# RCM-Comm_v1_no_ethernet.net
KiCad netlist of a schematic drawn in EAGLE
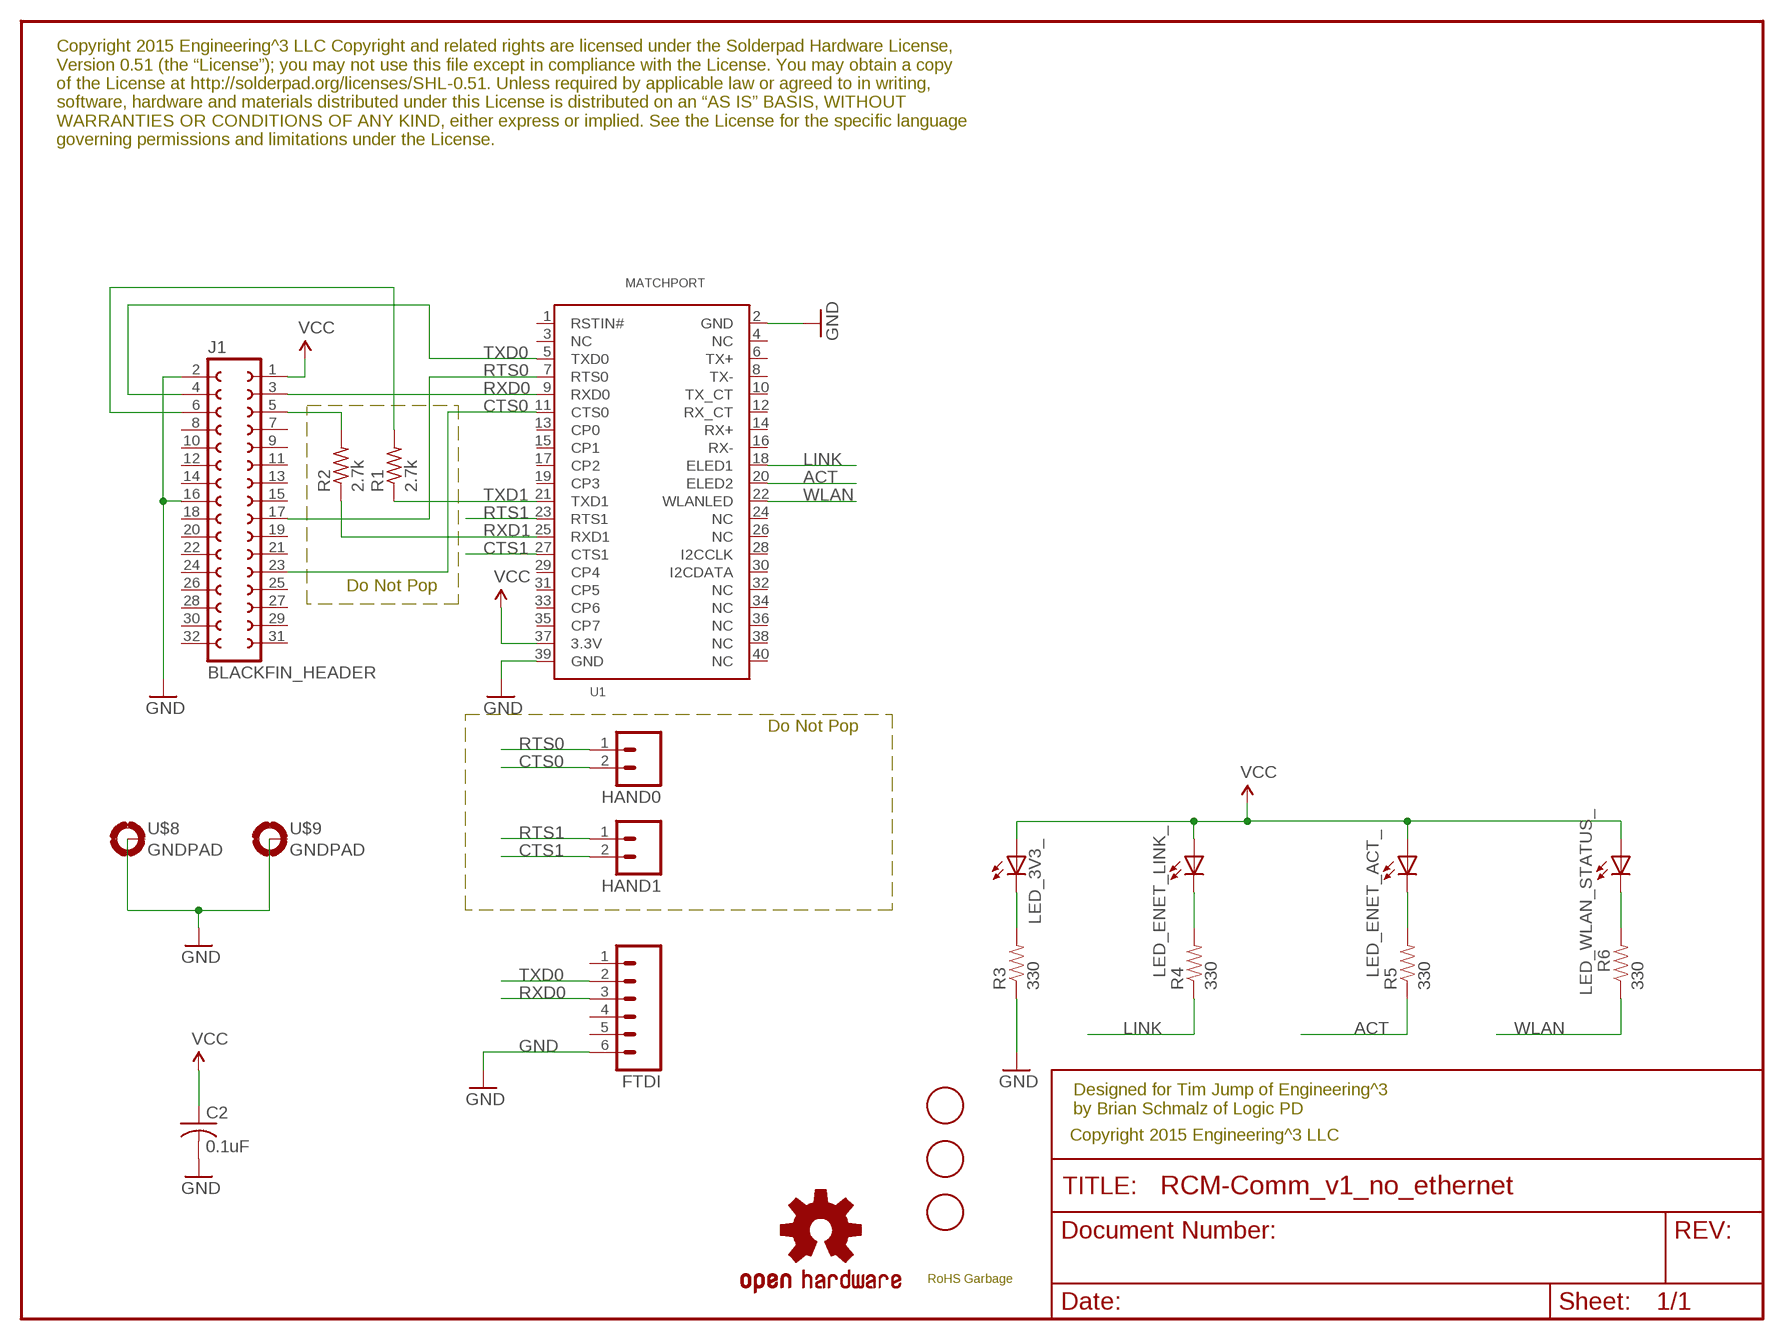
[diagram p0: schematic, sheet 1]

(export (version "E")
  (design (tool "Eeschema 10.0.6"))
  (components
    (comp (ref "C2")
      (value "0.1uF")
      (footprint "eagle-import:C0603")
      (libsource (lib "eagle-import") (part "C-USC0603"))
    )
    (comp (ref "FID1")
      (value "FIDUCIAL")
      (footprint "eagle-import:FIDUCIAL_1MM")
      (libsource (lib "eagle-import") (part "FIDUCIAL"))
    )
    (comp (ref "FID2")
      (value "FIDUCIAL")
      (footprint "eagle-import:FIDUCIAL_1MM")
      (libsource (lib "eagle-import") (part "FIDUCIAL"))
    )
    (comp (ref "FID3")
      (value "FIDUCIAL")
      (footprint "eagle-import:FIDUCIAL_1MM")
      (libsource (lib "eagle-import") (part "FIDUCIAL"))
    )
    (comp (ref "FTDI")
      (value "M06SIP")
      (footprint "eagle-import:1X06")
      (libsource (lib "eagle-import") (part "M06SIP"))
    )
    (comp (ref "HAND0")
      (value "M02PTH")
      (footprint "eagle-import:1X02")
      (libsource (lib "eagle-import") (part "M02PTH"))
    )
    (comp (ref "HAND1")
      (value "M02PTH")
      (footprint "eagle-import:1X02")
      (libsource (lib "eagle-import") (part "M02PTH"))
    )
    (comp (ref "J1")
      (value "BLACKFIN_HEADER")
      (footprint "eagle-import:2X16")
      (libsource (lib "eagle-import") (part "BLACKFIN_HEADER"))
    )
    (comp (ref "LED_3V3_")
      (value "LED0603")
      (footprint "eagle-import:LED-0603")
      (libsource (lib "eagle-import") (part "LED0603"))
    )
    (comp (ref "LED_ENET_ACT_")
      (value "LED0603")
      (footprint "eagle-import:LED-0603")
      (libsource (lib "eagle-import") (part "LED0603"))
    )
    (comp (ref "LED_ENET_LINK_")
      (value "LED0603")
      (footprint "eagle-import:LED-0603")
      (libsource (lib "eagle-import") (part "LED0603"))
    )
    (comp (ref "LED_WLAN_STATUS_")
      (value "LED0603")
      (footprint "eagle-import:LED-0603")
      (libsource (lib "eagle-import") (part "LED0603"))
    )
    (comp (ref "LOGO1")
      (value "OSHW-LOGOM")
      (footprint "eagle-import:OSHW-LOGO-M")
      (libsource (lib "eagle-import") (part "OSHW-LOGOM"))
    )
    (comp (ref "R1")
      (value "2.7k")
      (footprint "eagle-import:0207_10")
      (libsource (lib "eagle-import") (part "R-US_0207/10"))
    )
    (comp (ref "R2")
      (value "2.7k")
      (footprint "eagle-import:0207_10")
      (libsource (lib "eagle-import") (part "R-US_0207/10"))
    )
    (comp (ref "R3")
      (value "330")
      (footprint "eagle-import:0603-RES")
      (libsource (lib "eagle-import") (part "RESISTOR0603-RES"))
    )
    (comp (ref "R4")
      (value "330")
      (footprint "eagle-import:0603-RES")
      (libsource (lib "eagle-import") (part "RESISTOR0603-RES"))
    )
    (comp (ref "R5")
      (value "330")
      (footprint "eagle-import:0603-RES")
      (libsource (lib "eagle-import") (part "RESISTOR0603-RES"))
    )
    (comp (ref "R6")
      (value "330")
      (footprint "eagle-import:0603-RES")
      (libsource (lib "eagle-import") (part "RESISTOR0603-RES"))
    )
    (comp (ref "U$3")
      (value "ROHS_GARBAGE")
      (footprint "eagle-import:ROHS_GARBAGE_5MM")
      (libsource (lib "eagle-import") (part "ROHS_GARBAGE"))
    )
    (comp (ref "U$8")
      (value "GNDPAD")
      (footprint "eagle-import:GNDPAD")
      (libsource (lib "eagle-import") (part "GNDPAD"))
    )
    (comp (ref "U$9")
      (value "GNDPAD")
      (footprint "eagle-import:GNDPAD")
      (libsource (lib "eagle-import") (part "GNDPAD"))
    )
    (comp (ref "U1")
      (value "MATCHPORT")
      (footprint "eagle-import:MATCHPORT_LAYOUT")
      (libsource (lib "eagle-import") (part "MATCHPORT"))
    )
  )
  (nets
    (net (code "1") (name "/ACT") (class "Default")
      (node (ref "R5") (pin "1") (pinfunction "1_1") (pintype "passive"))
      (node (ref "U1") (pin "20") (pinfunction "ELED2_20") (pintype "bidirectional"))
    )
    (net (code "2") (name "/CTS0") (class "Default")
      (node (ref "HAND0") (pin "2") (pinfunction "2_2") (pintype "passive"))
      (node (ref "J1") (pin "23") (pinfunction "GP6_23") (pintype "passive"))
      (node (ref "U1") (pin "11") (pinfunction "CTS0_11") (pintype "bidirectional"))
    )
    (net (code "3") (name "/CTS1") (class "Default")
      (node (ref "HAND1") (pin "2") (pinfunction "2_2") (pintype "passive"))
      (node (ref "U1") (pin "27") (pinfunction "CTS1_27") (pintype "bidirectional"))
    )
    (net (code "4") (name "/LINK") (class "Default")
      (node (ref "R4") (pin "1") (pinfunction "1_1") (pintype "passive"))
      (node (ref "U1") (pin "18") (pinfunction "ELED1_18") (pintype "bidirectional"))
    )
    (net (code "5") (name "/RTS0") (class "Default")
      (node (ref "HAND0") (pin "1") (pinfunction "1_1") (pintype "passive"))
      (node (ref "J1") (pin "17") (pinfunction "GP0_17") (pintype "passive"))
      (node (ref "U1") (pin "7") (pinfunction "RTS0_7") (pintype "bidirectional"))
    )
    (net (code "6") (name "/RTS1") (class "Default")
      (node (ref "HAND1") (pin "1") (pinfunction "1_1") (pintype "passive"))
      (node (ref "U1") (pin "23") (pinfunction "RTS1_23") (pintype "bidirectional"))
    )
    (net (code "7") (name "/RXD0") (class "Default")
      (node (ref "FTDI") (pin "3") (pinfunction "3_3") (pintype "passive"))
      (node (ref "J1") (pin "3") (pinfunction "TX0_3") (pintype "passive"))
      (node (ref "U1") (pin "9") (pinfunction "RXD0_9") (pintype "bidirectional"))
    )
    (net (code "8") (name "/RXD1") (class "Default")
      (node (ref "R2") (pin "1") (pinfunction "1_1") (pintype "passive"))
      (node (ref "U1") (pin "25") (pinfunction "RXD1_25") (pintype "bidirectional"))
    )
    (net (code "9") (name "/TXD0") (class "Default")
      (node (ref "FTDI") (pin "2") (pinfunction "2_2") (pintype "passive"))
      (node (ref "J1") (pin "4") (pinfunction "RX0_4") (pintype "passive"))
      (node (ref "U1") (pin "5") (pinfunction "TXD0_5") (pintype "bidirectional"))
    )
    (net (code "10") (name "/TXD1") (class "Default")
      (node (ref "R1") (pin "1") (pinfunction "1_1") (pintype "passive"))
      (node (ref "U1") (pin "21") (pinfunction "TXD1_21") (pintype "bidirectional"))
    )
    (net (code "11") (name "/WLAN") (class "Default")
      (node (ref "R6") (pin "1") (pinfunction "1_1") (pintype "passive"))
      (node (ref "U1") (pin "22") (pinfunction "WLANLED_22") (pintype "bidirectional"))
    )
    (net (code "12") (name "GND") (class "Default")
      (node (ref "C2") (pin "2") (pinfunction "2_2") (pintype "passive"))
      (node (ref "FTDI") (pin "6") (pinfunction "6_6") (pintype "passive"))
      (node (ref "J1") (pin "16") (pinfunction "GND16_16") (pintype "passive"))
      (node (ref "J1") (pin "2") (pinfunction "GND_2") (pintype "passive"))
      (node (ref "R3") (pin "1") (pinfunction "1_1") (pintype "passive"))
      (node (ref "U$8") (pin "P$1") (pinfunction "MOUNT_P$1") (pintype "passive"))
      (node (ref "U$9") (pin "P$1") (pinfunction "MOUNT_P$1") (pintype "passive"))
      (node (ref "U1") (pin "2") (pinfunction "GND_2") (pintype "bidirectional"))
      (node (ref "U1") (pin "39") (pinfunction "GND_39") (pintype "bidirectional"))
    )
    (net (code "13") (name "Net-(J1-RX1)") (class "Default")
      (node (ref "J1") (pin "6") (pinfunction "RX1_6") (pintype "passive"))
      (node (ref "R1") (pin "2") (pinfunction "2_2") (pintype "passive"))
    )
    (net (code "14") (name "Net-(J1-TX1)") (class "Default")
      (node (ref "J1") (pin "5") (pinfunction "TX1_5") (pintype "passive"))
      (node (ref "R2") (pin "2") (pinfunction "2_2") (pintype "passive"))
    )
    (net (code "15") (name "Net-(LED_3V3_-PadC)") (class "Default")
      (node (ref "LED_3V3_") (pin "C") (pinfunction "C_C") (pintype "passive"))
      (node (ref "R3") (pin "2") (pinfunction "2_2") (pintype "passive"))
    )
    (net (code "16") (name "Net-(LED_ENET_ACT_-PadC)") (class "Default")
      (node (ref "LED_ENET_ACT_") (pin "C") (pinfunction "C_C") (pintype "passive"))
      (node (ref "R5") (pin "2") (pinfunction "2_2") (pintype "passive"))
    )
    (net (code "17") (name "Net-(LED_ENET_LINK_-PadC)") (class "Default")
      (node (ref "LED_ENET_LINK_") (pin "C") (pinfunction "C_C") (pintype "passive"))
      (node (ref "R4") (pin "2") (pinfunction "2_2") (pintype "passive"))
    )
    (net (code "18") (name "Net-(LED_WLAN_STATUS_-PadC)") (class "Default")
      (node (ref "LED_WLAN_STATUS_") (pin "C") (pinfunction "C_C") (pintype "passive"))
      (node (ref "R6") (pin "2") (pinfunction "2_2") (pintype "passive"))
    )
    (net (code "19") (name "VCC") (class "Default")
      (node (ref "C2") (pin "1") (pinfunction "1_1") (pintype "passive"))
      (node (ref "J1") (pin "1") (pinfunction "3.3V_1") (pintype "passive"))
      (node (ref "LED_3V3_") (pin "A") (pinfunction "A_A") (pintype "passive"))
      (node (ref "LED_ENET_ACT_") (pin "A") (pinfunction "A_A") (pintype "passive"))
      (node (ref "LED_ENET_LINK_") (pin "A") (pinfunction "A_A") (pintype "passive"))
      (node (ref "LED_WLAN_STATUS_") (pin "A") (pinfunction "A_A") (pintype "passive"))
      (node (ref "U1") (pin "37") (pinfunction "3.3V_37") (pintype "bidirectional"))
    )
    (net (code "20") (name "unconnected-(FTDI-Pad1)") (class "Default")
      (node (ref "FTDI") (pin "1") (pinfunction "1_1") (pintype "passive"))
    )
    (net (code "21") (name "unconnected-(FTDI-Pad4)") (class "Default")
      (node (ref "FTDI") (pin "4") (pinfunction "4_4") (pintype "passive"))
    )
    (net (code "22") (name "unconnected-(FTDI-Pad5)") (class "Default")
      (node (ref "FTDI") (pin "5") (pinfunction "5_5") (pintype "passive"))
    )
    (net (code "23") (name "unconnected-(J1-GP1-Pad18)") (class "Default")
      (node (ref "J1") (pin "18") (pinfunction "GP1_18") (pintype "passive"))
    )
    (net (code "24") (name "unconnected-(J1-GP2-Pad19)") (class "Default")
      (node (ref "J1") (pin "19") (pinfunction "GP2_19") (pintype "passive"))
    )
    (net (code "25") (name "unconnected-(J1-GP3-Pad20)") (class "Default")
      (node (ref "J1") (pin "20") (pinfunction "GP3_20") (pintype "passive"))
    )
    (net (code "26") (name "unconnected-(J1-GP4-Pad21)") (class "Default")
      (node (ref "J1") (pin "21") (pinfunction "GP4_21") (pintype "passive"))
    )
    (net (code "27") (name "unconnected-(J1-GP5-Pad22)") (class "Default")
      (node (ref "J1") (pin "22") (pinfunction "GP5_22") (pintype "passive"))
    )
    (net (code "28") (name "unconnected-(J1-GP7-Pad24)") (class "Default")
      (node (ref "J1") (pin "24") (pinfunction "GP7_24") (pintype "passive"))
    )
    (net (code "29") (name "unconnected-(J1-GP8-Pad25)") (class "Default")
      (node (ref "J1") (pin "25") (pinfunction "GP8_25") (pintype "passive"))
    )
    (net (code "30") (name "unconnected-(J1-GP9-Pad26)") (class "Default")
      (node (ref "J1") (pin "26") (pinfunction "GP9_26") (pintype "passive"))
    )
    (net (code "31") (name "unconnected-(J1-GPA-Pad27)") (class "Default")
      (node (ref "J1") (pin "27") (pinfunction "GPA_27") (pintype "passive"))
    )
    (net (code "32") (name "unconnected-(J1-GPB-Pad28)") (class "Default")
      (node (ref "J1") (pin "28") (pinfunction "GPB_28") (pintype "passive"))
    )
    (net (code "33") (name "unconnected-(J1-GPC-Pad29)") (class "Default")
      (node (ref "J1") (pin "29") (pinfunction "GPC_29") (pintype "passive"))
    )
    (net (code "34") (name "unconnected-(J1-GPD-Pad30)") (class "Default")
      (node (ref "J1") (pin "30") (pinfunction "GPD_30") (pintype "passive"))
    )
    (net (code "35") (name "unconnected-(J1-GPE-Pad31)") (class "Default")
      (node (ref "J1") (pin "31") (pinfunction "GPE_31") (pintype "passive"))
    )
    (net (code "36") (name "unconnected-(J1-GPF-Pad32)") (class "Default")
      (node (ref "J1") (pin "32") (pinfunction "GPF_32") (pintype "passive"))
    )
    (net (code "37") (name "unconnected-(J1-I2C_SDA-Pad15)") (class "Default")
      (node (ref "J1") (pin "15") (pinfunction "I2C_SDA_15") (pintype "passive"))
    )
    (net (code "38") (name "unconnected-(J1-SPI_MISO-Pad10)") (class "Default")
      (node (ref "J1") (pin "10") (pinfunction "SPI_MISO_10") (pintype "passive"))
    )
    (net (code "39") (name "unconnected-(J1-SPI_MOSI-Pad9)") (class "Default")
      (node (ref "J1") (pin "9") (pinfunction "SPI_MOSI_9") (pintype "passive"))
    )
    (net (code "40") (name "unconnected-(J1-SPI_SCK-Pad11)") (class "Default")
      (node (ref "J1") (pin "11") (pinfunction "SPI_SCK_11") (pintype "passive"))
    )
    (net (code "41") (name "unconnected-(J1-SPI_SCL-Pad14)") (class "Default")
      (node (ref "J1") (pin "14") (pinfunction "SPI_SCL_14") (pintype "passive"))
    )
    (net (code "42") (name "unconnected-(J1-SPI_SEL-Pad12)") (class "Default")
      (node (ref "J1") (pin "12") (pinfunction "SPI_SEL_12") (pintype "passive"))
    )
    (net (code "43") (name "unconnected-(J1-SPI_SEL2-Pad13)") (class "Default")
      (node (ref "J1") (pin "13") (pinfunction "SPI_SEL2_13") (pintype "passive"))
    )
    (net (code "44") (name "unconnected-(J1-TMR2-Pad7)") (class "Default")
      (node (ref "J1") (pin "7") (pinfunction "TMR2_7") (pintype "passive"))
    )
    (net (code "45") (name "unconnected-(J1-TMR3-Pad8)") (class "Default")
      (node (ref "J1") (pin "8") (pinfunction "TMR3_8") (pintype "passive"))
    )
    (net (code "46") (name "unconnected-(U1-CP0-Pad13)") (class "Default")
      (node (ref "U1") (pin "13") (pinfunction "CP0_13") (pintype "bidirectional"))
    )
    (net (code "47") (name "unconnected-(U1-CP1-Pad15)") (class "Default")
      (node (ref "U1") (pin "15") (pinfunction "CP1_15") (pintype "bidirectional"))
    )
    (net (code "48") (name "unconnected-(U1-CP2-Pad17)") (class "Default")
      (node (ref "U1") (pin "17") (pinfunction "CP2_17") (pintype "bidirectional"))
    )
    (net (code "49") (name "unconnected-(U1-CP3-Pad19)") (class "Default")
      (node (ref "U1") (pin "19") (pinfunction "CP3_19") (pintype "bidirectional"))
    )
    (net (code "50") (name "unconnected-(U1-CP4-Pad29)") (class "Default")
      (node (ref "U1") (pin "29") (pinfunction "CP4_29") (pintype "bidirectional"))
    )
    (net (code "51") (name "unconnected-(U1-CP5-Pad31)") (class "Default")
      (node (ref "U1") (pin "31") (pinfunction "CP5_31") (pintype "bidirectional"))
    )
    (net (code "52") (name "unconnected-(U1-CP6-Pad33)") (class "Default")
      (node (ref "U1") (pin "33") (pinfunction "CP6_33") (pintype "bidirectional"))
    )
    (net (code "53") (name "unconnected-(U1-CP7-Pad35)") (class "Default")
      (node (ref "U1") (pin "35") (pinfunction "CP7_35") (pintype "bidirectional"))
    )
    (net (code "54") (name "unconnected-(U1-I2CCLK-Pad28)") (class "Default")
      (node (ref "U1") (pin "28") (pinfunction "I2CCLK_28") (pintype "bidirectional"))
    )
    (net (code "55") (name "unconnected-(U1-I2CDATA-Pad30)") (class "Default")
      (node (ref "U1") (pin "30") (pinfunction "I2CDATA_30") (pintype "bidirectional"))
    )
    (net (code "56") (name "unconnected-(U1-NC-Pad3)") (class "Default")
      (node (ref "U1") (pin "3") (pinfunction "NC_3") (pintype "no_connect"))
    )
    (net (code "57") (name "unconnected-(U1-NC-Pad4)") (class "Default")
      (node (ref "U1") (pin "4") (pinfunction "NC_4") (pintype "no_connect"))
    )
    (net (code "58") (name "unconnected-(U1-NC-Pad24)") (class "Default")
      (node (ref "U1") (pin "24") (pinfunction "NC_24") (pintype "no_connect"))
    )
    (net (code "59") (name "unconnected-(U1-NC-Pad26)") (class "Default")
      (node (ref "U1") (pin "26") (pinfunction "NC_26") (pintype "no_connect"))
    )
    (net (code "60") (name "unconnected-(U1-NC-Pad32)") (class "Default")
      (node (ref "U1") (pin "32") (pinfunction "NC_32") (pintype "no_connect"))
    )
    (net (code "61") (name "unconnected-(U1-NC-Pad34)") (class "Default")
      (node (ref "U1") (pin "34") (pinfunction "NC_34") (pintype "no_connect"))
    )
    (net (code "62") (name "unconnected-(U1-NC-Pad36)") (class "Default")
      (node (ref "U1") (pin "36") (pinfunction "NC_36") (pintype "no_connect"))
    )
    (net (code "63") (name "unconnected-(U1-NC-Pad38)") (class "Default")
      (node (ref "U1") (pin "38") (pinfunction "NC_38") (pintype "no_connect"))
    )
    (net (code "64") (name "unconnected-(U1-NC-Pad40)") (class "Default")
      (node (ref "U1") (pin "40") (pinfunction "NC_40") (pintype "no_connect"))
    )
    (net (code "65") (name "unconnected-(U1-RSTIN#-Pad1)") (class "Default")
      (node (ref "U1") (pin "1") (pinfunction "RSTIN#_1") (pintype "bidirectional"))
    )
    (net (code "66") (name "unconnected-(U1-RX+-Pad14)") (class "Default")
      (node (ref "U1") (pin "14") (pinfunction "RX+_14") (pintype "bidirectional"))
    )
    (net (code "67") (name "unconnected-(U1-RX--Pad16)") (class "Default")
      (node (ref "U1") (pin "16") (pinfunction "RX-_16") (pintype "bidirectional"))
    )
    (net (code "68") (name "unconnected-(U1-RX_CT-Pad12)") (class "Default")
      (node (ref "U1") (pin "12") (pinfunction "RX_CT_12") (pintype "bidirectional"))
    )
    (net (code "69") (name "unconnected-(U1-TX+-Pad6)") (class "Default")
      (node (ref "U1") (pin "6") (pinfunction "TX+_6") (pintype "bidirectional"))
    )
    (net (code "70") (name "unconnected-(U1-TX--Pad8)") (class "Default")
      (node (ref "U1") (pin "8") (pinfunction "TX-_8") (pintype "bidirectional"))
    )
    (net (code "71") (name "unconnected-(U1-TX_CT-Pad10)") (class "Default")
      (node (ref "U1") (pin "10") (pinfunction "TX_CT_10") (pintype "bidirectional"))
    )
  )
)
